# IOExpansion.net
KiCad netlist of a schematic drawn in EAGLE
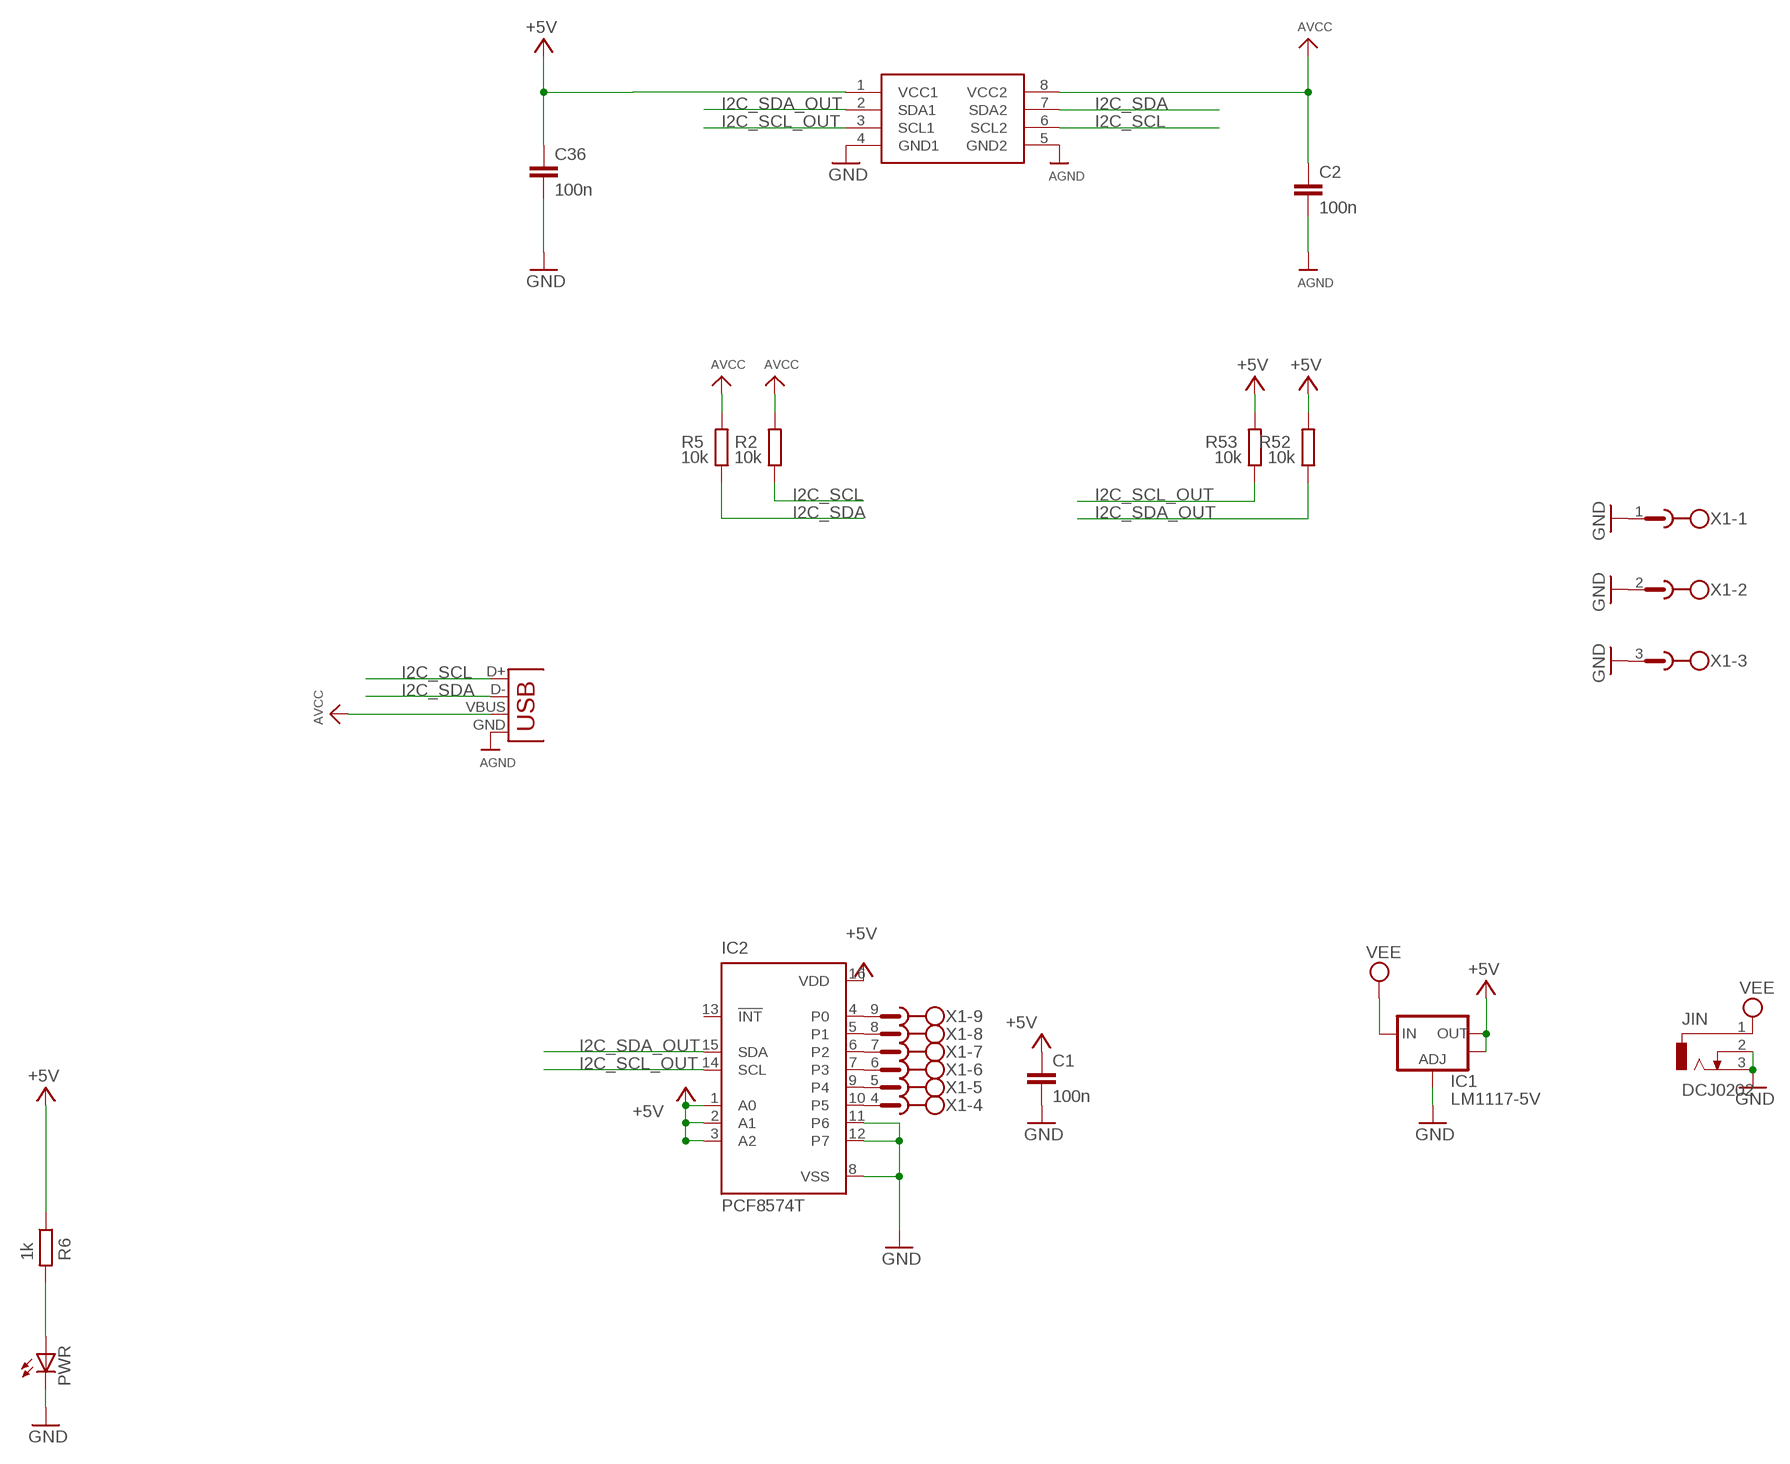
[diagram p0: schematic, sheet 1]

(export (version "E")
  (design (tool "Eeschema 10.0.6"))
  (components
    (comp (ref "C1")
      (value "100n")
      (footprint "eagle-import:C0805")
      (libsource (lib "eagle-import") (part "C-EUC0805"))
    )
    (comp (ref "C2")
      (value "100n")
      (footprint "eagle-import:C0805")
      (libsource (lib "eagle-import") (part "C-EUC0805"))
    )
    (comp (ref "C36")
      (value "100n")
      (footprint "eagle-import:C0805")
      (libsource (lib "eagle-import") (part "C-EUC0805"))
    )
    (comp (ref "IC1")
      (value "LM1117-5V")
      (footprint "eagle-import:SOT223")
      (libsource (lib "eagle-import") (part "V_REG_LM1117SOT223"))
    )
    (comp (ref "IC2")
      (value "PCF8574T")
      (footprint "eagle-import:SO16W")
      (libsource (lib "eagle-import") (part "PCF8574T"))
    )
    (comp (ref "JIN")
      (value "DCJ0202")
      (footprint "eagle-import:DCJ0202")
      (libsource (lib "eagle-import") (part "DCJ0202"))
    )
    (comp (ref "PWR")
      (value "LED3MM")
      (footprint "eagle-import:LED3MM")
      (libsource (lib "eagle-import") (part "LED3MM"))
    )
    (comp (ref "R2")
      (value "10k")
      (footprint "eagle-import:R0805")
      (libsource (lib "eagle-import") (part "R-EU_R0805"))
    )
    (comp (ref "R5")
      (value "10k")
      (footprint "eagle-import:R0805")
      (libsource (lib "eagle-import") (part "R-EU_R0805"))
    )
    (comp (ref "R6")
      (value "1k")
      (footprint "eagle-import:R0805")
      (libsource (lib "eagle-import") (part "R-EU_R0805"))
    )
    (comp (ref "R52")
      (value "10k")
      (footprint "eagle-import:R0805")
      (libsource (lib "eagle-import") (part "R-EU_R0805"))
    )
    (comp (ref "R53")
      (value "10k")
      (footprint "eagle-import:R0805")
      (libsource (lib "eagle-import") (part "R-EU_R0805"))
    )
    (comp (ref "U2")
      (value "ADUM1250")
      (footprint "eagle-import:SO08")
      (libsource (lib "eagle-import") (part "ADUM1250"))
    )
    (comp (ref "X1")
      (value "MSTBV9")
      (footprint "eagle-import:MSTBV9")
      (libsource (lib "eagle-import") (part "MSTBV9"))
    )
    (comp (ref "X5")
      (value "USBSMD")
      (footprint "eagle-import:USB-MINIB")
      (libsource (lib "eagle-import") (part "USBSMD"))
    )
  )
  (nets
    (net (code "1") (name "+5V") (class "Default")
      (node (ref "C1") (pin "1") (pinfunction "1_1") (pintype "passive"))
      (node (ref "C36") (pin "1") (pinfunction "1_1") (pintype "passive"))
      (node (ref "IC1") (pin "2") (pinfunction "OUT_2") (pintype "output"))
      (node (ref "IC1") (pin "4") (pinfunction "OUT_4") (pintype "output"))
      (node (ref "IC2") (pin "1") (pinfunction "A0_1") (pintype "input"))
      (node (ref "IC2") (pin "16") (pinfunction "VDD_16") (pintype "power_in"))
      (node (ref "IC2") (pin "2") (pinfunction "A1_2") (pintype "input"))
      (node (ref "IC2") (pin "3") (pinfunction "A2_3") (pintype "input"))
      (node (ref "R52") (pin "2") (pinfunction "2_2") (pintype "passive"))
      (node (ref "R53") (pin "2") (pinfunction "2_2") (pintype "passive"))
      (node (ref "R6") (pin "1") (pinfunction "1_1") (pintype "passive"))
      (node (ref "U2") (pin "1") (pinfunction "VCC1_1") (pintype "bidirectional"))
    )
    (net (code "2") (name "/I2C_SCL") (class "Default")
      (node (ref "R2") (pin "1") (pinfunction "1_1") (pintype "passive"))
      (node (ref "U2") (pin "6") (pinfunction "SCL2_6") (pintype "bidirectional"))
      (node (ref "X5") (pin "D+") (pinfunction "D+_D+") (pintype "bidirectional"))
    )
    (net (code "3") (name "/I2C_SCL_OUT") (class "Default")
      (node (ref "IC2") (pin "14") (pinfunction "SCL_14") (pintype "input"))
      (node (ref "R53") (pin "1") (pinfunction "1_1") (pintype "passive"))
      (node (ref "U2") (pin "3") (pinfunction "SCL1_3") (pintype "bidirectional"))
    )
    (net (code "4") (name "/I2C_SDA") (class "Default")
      (node (ref "R5") (pin "1") (pinfunction "1_1") (pintype "passive"))
      (node (ref "U2") (pin "7") (pinfunction "SDA2_7") (pintype "bidirectional"))
      (node (ref "X5") (pin "D-") (pinfunction "D-_D-") (pintype "bidirectional"))
    )
    (net (code "5") (name "/I2C_SDA_OUT") (class "Default")
      (node (ref "IC2") (pin "15") (pinfunction "SDA_15") (pintype "bidirectional"))
      (node (ref "R52") (pin "1") (pinfunction "1_1") (pintype "passive"))
      (node (ref "U2") (pin "2") (pinfunction "SDA1_2") (pintype "bidirectional"))
    )
    (net (code "6") (name "AGND") (class "Default")
      (node (ref "C2") (pin "2") (pinfunction "2_2") (pintype "passive"))
      (node (ref "U2") (pin "5") (pinfunction "GND2_5") (pintype "bidirectional"))
      (node (ref "X5") (pin "GND") (pinfunction "GND_GND") (pintype "bidirectional"))
    )
    (net (code "7") (name "AVCC") (class "Default")
      (node (ref "C2") (pin "1") (pinfunction "1_1") (pintype "passive"))
      (node (ref "R2") (pin "2") (pinfunction "2_2") (pintype "passive"))
      (node (ref "R5") (pin "2") (pinfunction "2_2") (pintype "passive"))
      (node (ref "U2") (pin "8") (pinfunction "VCC2_8") (pintype "bidirectional"))
      (node (ref "X5") (pin "VBUS") (pinfunction "VBUS_VBUS") (pintype "bidirectional"))
    )
    (net (code "8") (name "GND") (class "Default")
      (node (ref "C1") (pin "2") (pinfunction "2_2") (pintype "passive"))
      (node (ref "C36") (pin "2") (pinfunction "2_2") (pintype "passive"))
      (node (ref "IC1") (pin "1") (pinfunction "ADJ_1") (pintype "input"))
      (node (ref "IC2") (pin "11") (pinfunction "P6_11") (pintype "bidirectional"))
      (node (ref "IC2") (pin "12") (pinfunction "P7_12") (pintype "bidirectional"))
      (node (ref "IC2") (pin "8") (pinfunction "VSS_8") (pintype "power_in"))
      (node (ref "JIN") (pin "2") (pinfunction "2_2") (pintype "passive"))
      (node (ref "JIN") (pin "3") (pinfunction "3_3") (pintype "passive"))
      (node (ref "PWR") (pin "K") (pinfunction "C_K") (pintype "passive"))
      (node (ref "U2") (pin "4") (pinfunction "GND1_4") (pintype "bidirectional"))
      (node (ref "X1") (pin "1") (pinfunction "1_1") (pintype "passive"))
      (node (ref "X1") (pin "2") (pinfunction "1_2") (pintype "passive"))
      (node (ref "X1") (pin "3") (pinfunction "1_3") (pintype "passive"))
    )
    (net (code "9") (name "Net-(IC2-P0)") (class "Default")
      (node (ref "IC2") (pin "4") (pinfunction "P0_4") (pintype "bidirectional"))
      (node (ref "X1") (pin "9") (pinfunction "1_9") (pintype "passive"))
    )
    (net (code "10") (name "Net-(IC2-P1)") (class "Default")
      (node (ref "IC2") (pin "5") (pinfunction "P1_5") (pintype "bidirectional"))
      (node (ref "X1") (pin "8") (pinfunction "1_8") (pintype "passive"))
    )
    (net (code "11") (name "Net-(IC2-P2)") (class "Default")
      (node (ref "IC2") (pin "6") (pinfunction "P2_6") (pintype "bidirectional"))
      (node (ref "X1") (pin "7") (pinfunction "1_7") (pintype "passive"))
    )
    (net (code "12") (name "Net-(IC2-P3)") (class "Default")
      (node (ref "IC2") (pin "7") (pinfunction "P3_7") (pintype "bidirectional"))
      (node (ref "X1") (pin "6") (pinfunction "1_6") (pintype "passive"))
    )
    (net (code "13") (name "Net-(IC2-P4)") (class "Default")
      (node (ref "IC2") (pin "9") (pinfunction "P4_9") (pintype "bidirectional"))
      (node (ref "X1") (pin "5") (pinfunction "1_5") (pintype "passive"))
    )
    (net (code "14") (name "Net-(IC2-P5)") (class "Default")
      (node (ref "IC2") (pin "10") (pinfunction "P5_10") (pintype "bidirectional"))
      (node (ref "X1") (pin "4") (pinfunction "1_4") (pintype "passive"))
    )
    (net (code "15") (name "Net-(PWR-PadA)") (class "Default")
      (node (ref "PWR") (pin "A") (pinfunction "A_A") (pintype "passive"))
      (node (ref "R6") (pin "2") (pinfunction "2_2") (pintype "passive"))
    )
    (net (code "16") (name "VEE") (class "Default")
      (node (ref "IC1") (pin "3") (pinfunction "IN_3") (pintype "input"))
      (node (ref "JIN") (pin "1") (pinfunction "1_1") (pintype "passive"))
    )
    (net (code "17") (name "unconnected-(IC2-~{INT}-Pad13)") (class "Default")
      (node (ref "IC2") (pin "13") (pinfunction "~{INT}_13") (pintype "output"))
    )
  )
)
